# SwitchBypassWaveyRadar.net
KiCad netlist of a schematic drawn in Altium Designer
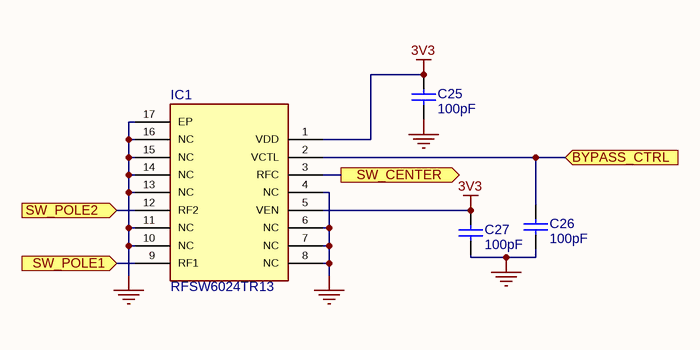
[diagram p0: SwitchBypassWaveyRadar.SchDoc]

(export (version "E")
  (design (tool "Eeschema 10.0.6"))
  (components
    (comp (ref "C25")
      (value "100pF")
      (footprint "CAPC1005X56X25LL10T15")
      (fields (field (name "Comment") "04023A101JAT2A"))
      (libsource (lib "University of South Florida") (part "CAP-NP-2"))
    )
    (comp (ref "C26")
      (value "100pF")
      (footprint "CAPC1005X56X25LL10T15")
      (fields (field (name "Comment") "04023A101JAT2A"))
      (libsource (lib "University of South Florida") (part "CAP-NP-2"))
    )
    (comp (ref "C27")
      (value "100pF")
      (footprint "CAPC1005X56X25LL10T15")
      (fields (field (name "Comment") "04023A101JAT2A"))
      (libsource (lib "University of South Florida") (part "CAP-NP-2"))
    )
    (comp (ref "IC1")
      (value "RFSW6024TR13")
      (footprint "QFN65P400X400X90-17N")
      (description "Integrated Circuit")
      (fields (field (name "MOUSER2 PART NUMBER") "772-RFSW6024TR13"))
      (libsource (lib "University of South Florida") (part "RFSW6024TR13"))
    )
  )
  (nets
    (net (code "1") (name "/BYPASS_CTRL") (class "Default")
      (node (ref "C26") (pin "1") (pinfunction "1_1") (pintype "passive"))
      (node (ref "IC1") (pin "2") (pinfunction "VCTL_2") (pintype "passive"))
    )
    (net (code "2") (name "/SW_CENTER") (class "Default")
      (node (ref "IC1") (pin "3") (pinfunction "RFC_3") (pintype "passive"))
    )
    (net (code "3") (name "/SW_POLE1") (class "Default")
      (node (ref "IC1") (pin "9") (pinfunction "RF1_9") (pintype "passive"))
    )
    (net (code "4") (name "/SW_POLE2") (class "Default")
      (node (ref "IC1") (pin "12") (pinfunction "RF2_12") (pintype "passive"))
    )
    (net (code "5") (name "3V3") (class "Default")
      (node (ref "C25") (pin "2") (pinfunction "2_2") (pintype "passive"))
      (node (ref "C27") (pin "1") (pinfunction "1_1") (pintype "passive"))
      (node (ref "IC1") (pin "1") (pinfunction "VDD_1") (pintype "power_in"))
      (node (ref "IC1") (pin "5") (pinfunction "VEN_5") (pintype "passive"))
    )
    (net (code "6") (name "GND") (class "Default")
      (node (ref "C25") (pin "1") (pinfunction "1_1") (pintype "passive"))
      (node (ref "C26") (pin "2") (pinfunction "2_2") (pintype "passive"))
      (node (ref "C27") (pin "2") (pinfunction "2_2") (pintype "passive"))
      (node (ref "IC1") (pin "10") (pinfunction "NC_10") (pintype "passive"))
      (node (ref "IC1") (pin "11") (pinfunction "NC_11") (pintype "passive"))
      (node (ref "IC1") (pin "13") (pinfunction "NC_13") (pintype "passive"))
      (node (ref "IC1") (pin "14") (pinfunction "NC_14") (pintype "passive"))
      (node (ref "IC1") (pin "15") (pinfunction "NC_15") (pintype "passive"))
      (node (ref "IC1") (pin "16") (pinfunction "NC_16") (pintype "passive"))
      (node (ref "IC1") (pin "17") (pinfunction "EP_17") (pintype "passive"))
      (node (ref "IC1") (pin "4") (pinfunction "NC_4") (pintype "passive"))
      (node (ref "IC1") (pin "6") (pinfunction "NC_6") (pintype "passive"))
      (node (ref "IC1") (pin "7") (pinfunction "NC_7") (pintype "passive"))
      (node (ref "IC1") (pin "8") (pinfunction "NC_8") (pintype "passive"))
    )
  )
)
